# 1_3.net
KiCad netlist of a schematic drawn in Altium Designer
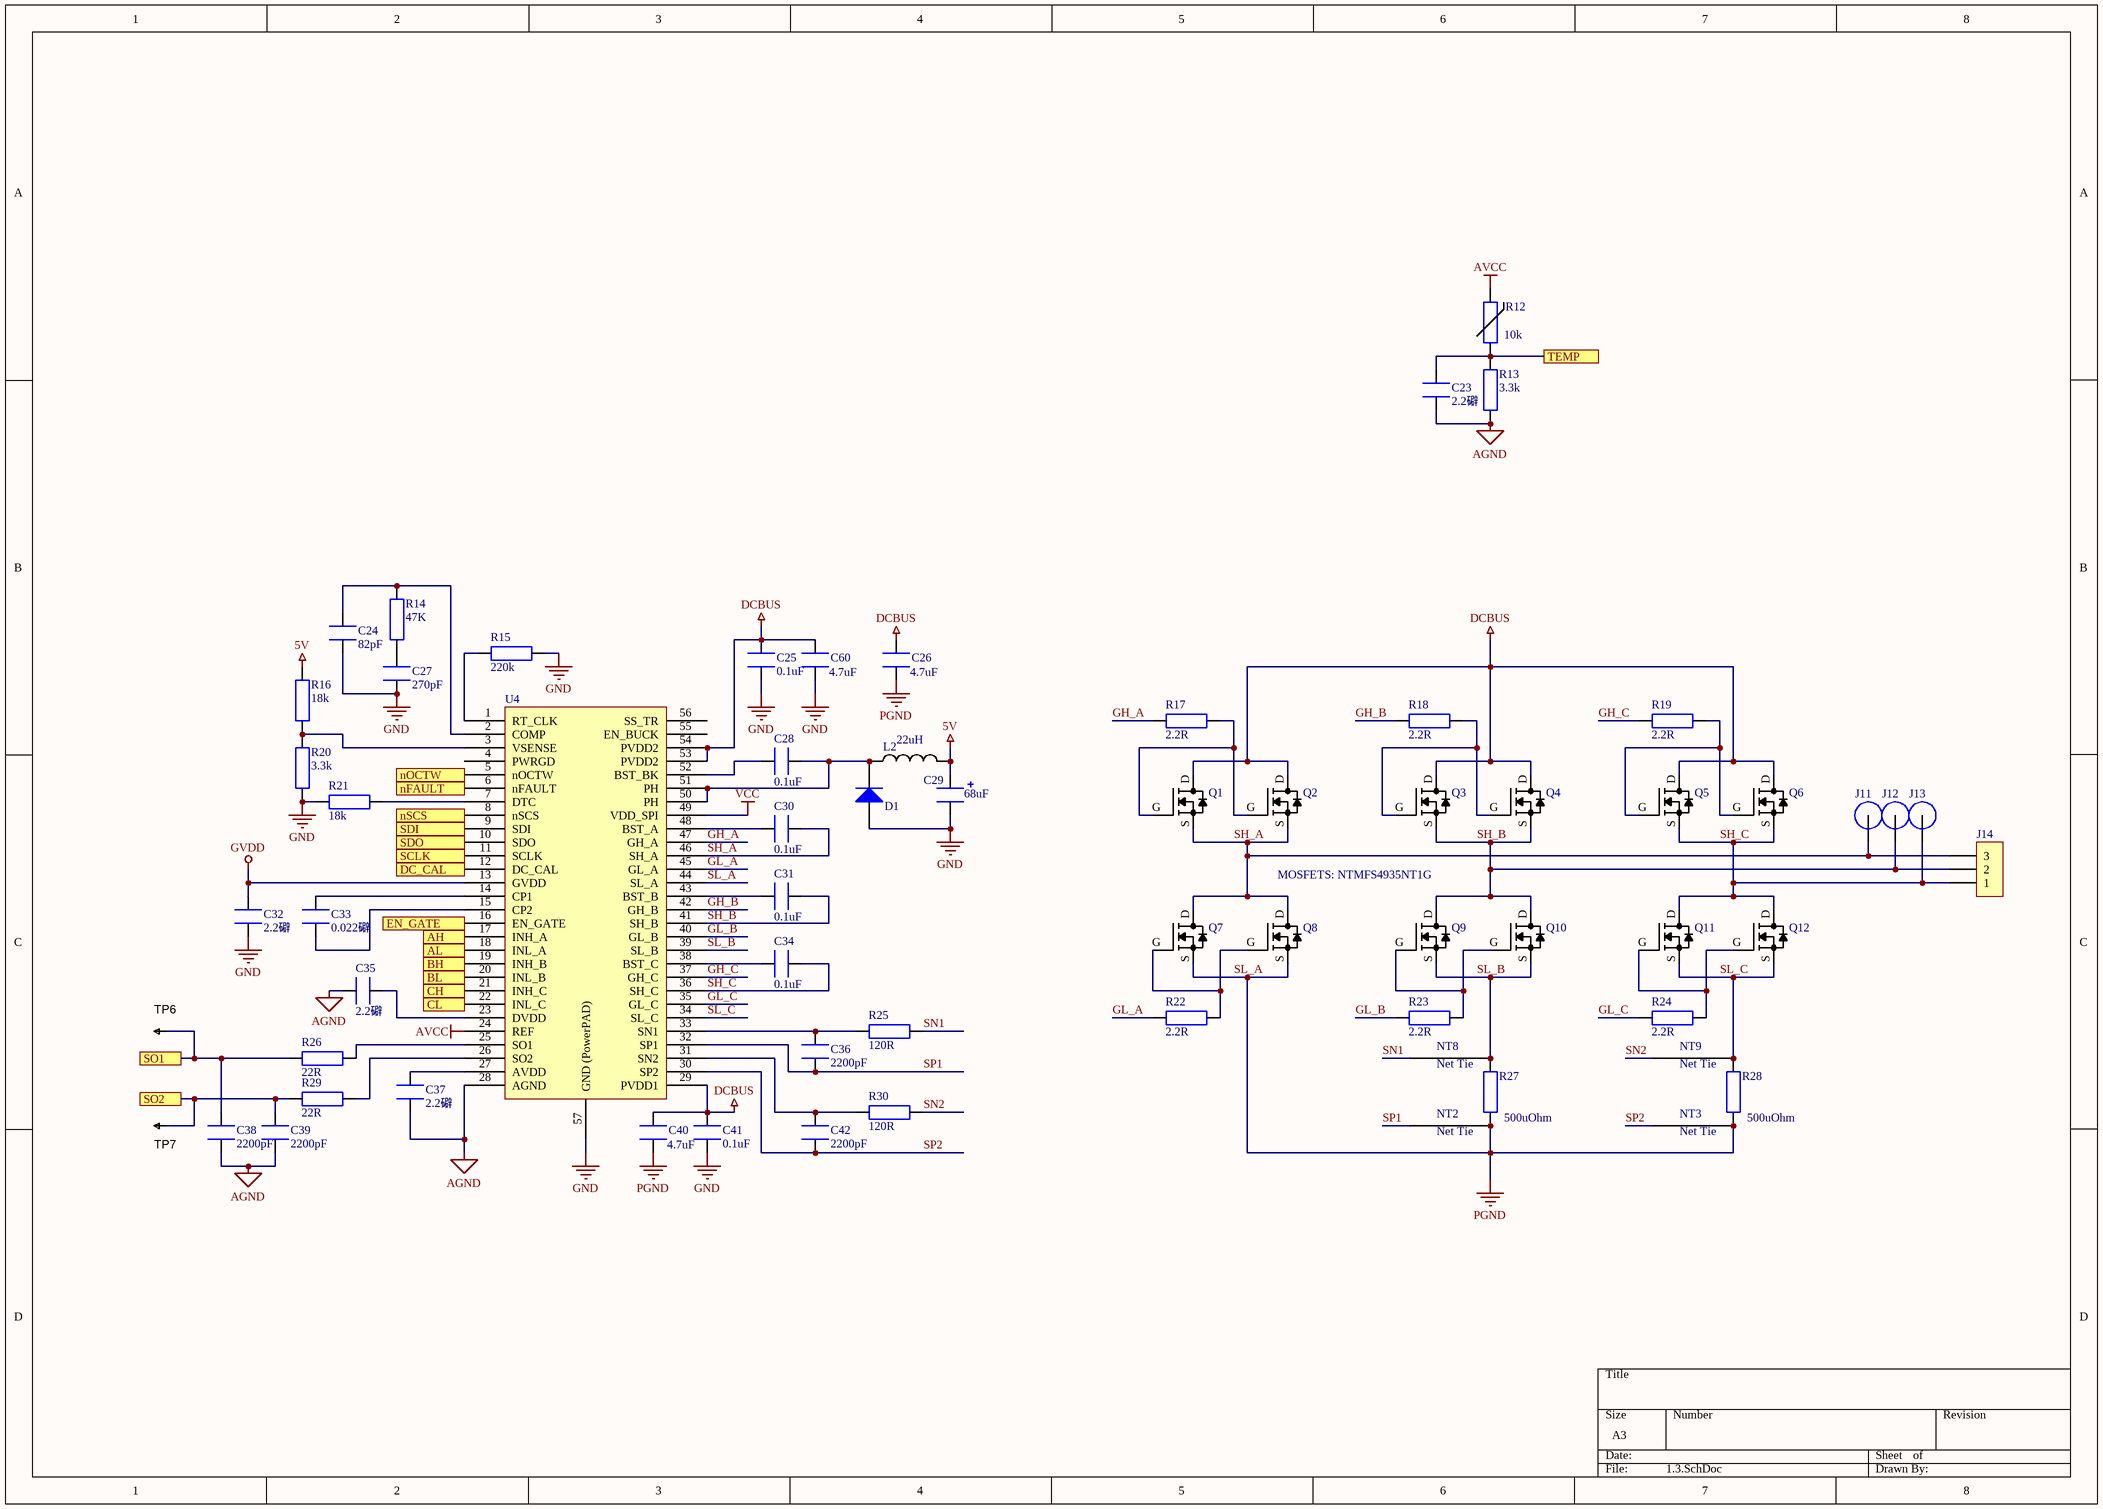
[diagram p0: 1.3.SchDoc]

(export (version "E")
  (design (tool "Eeschema 10.0.6"))
  (components
    (comp (ref "C23")
      (value "2.2礔")
      (footprint "CAPC1608X09L")
      (description "CAP CER 2.2UF 16V X5R 0603")
      (fields
        (field (name "MANUFACTURER") "Murata Electronics North America")
        (field (name "MANUFACTURER PART NUMBER") "GRM188R61C225KE15D")
      )
      (libsource (lib "CustomComponents") (part "GRM188R61C225KE15D"))
    )
    (comp (ref "C24")
      (value "82pF")
      (footprint "CAPC1608X09L")
      (description "CAP CER 82PF 100V NP0 0603")
      (fields
        (field (name "MANUFACTURER") "Murata Electronics North America")
        (field (name "MANUFACTURER PART NUMBER") "GRM1885C2A820JA01D")
      )
      (libsource (lib "CustomComponents") (part "GRM1885C2A820JA01D"))
    )
    (comp (ref "C25")
      (value "0.1uF")
      (footprint "CAPC1608X09L")
      (description "CAP CER 0.1UF 50V X7R 0603")
      (fields
        (field (name "MANUFACTURER") "Murata Electronics North America")
        (field (name "MANUFACTURER PART NUMBER") "GRM188R71H104KA93D")
      )
      (libsource (lib "CustomComponents") (part "GRM188R71H104KA93D"))
    )
    (comp (ref "C26")
      (value "4.7uF")
      (footprint "CAPC2012X09N")
      (description "CAP CER 4.7UF 35V X5R 0805")
      (fields
        (field (name "MANUFACTURER") "Murata Electronics North America")
        (field (name "TOLERANCE") "?0%")
      )
      (libsource (lib "CustomComponents") (part "GRM219R6YA475KA73D"))
    )
    (comp (ref "C27")
      (value "270pF")
      (footprint "CAPC1608X09L")
      (description "CAP CER 270PF 50V NP0 0603")
      (fields
        (field (name "MANUFACTURER") "Murata Electronics North America")
        (field (name "MANUFACTURER PART NUMBER") "GRM1885C1H271JA01D")
      )
      (libsource (lib "CustomComponents") (part "GRM1885C1H271JA01D"))
    )
    (comp (ref "C28")
      (value "0.1uF")
      (footprint "CAPC1608X09L")
      (description "CAP CER 0.1UF 50V X7R 0603")
      (fields
        (field (name "MANUFACTURER") "Murata Electronics North America")
        (field (name "MANUFACTURER PART NUMBER") "GRM188R71H104KA93D")
      )
      (libsource (lib "CustomComponents") (part "GRM188R71H104KA93D"))
    )
    (comp (ref "C29")
      (value "68uF")
      (footprint "CAPCP6032X28N")
      (description "CAP TANT 68UF 16V 20% 2312 250mOhm")
      (fields (field (name "MANUFACTURER") "KEMET") (field (name "TOLERANCE") "?0%"))
      (libsource (lib "CustomComponents") (part "T495C686M016ATE250"))
    )
    (comp (ref "C30")
      (value "0.1uF")
      (footprint "CAPC1608X09L")
      (description "CAP CER 0.1UF 50V X7R 0603")
      (fields
        (field (name "MANUFACTURER") "Murata Electronics North America")
        (field (name "MANUFACTURER PART NUMBER") "GRM188R71H104KA93D")
      )
      (libsource (lib "CustomComponents") (part "GRM188R71H104KA93D"))
    )
    (comp (ref "C31")
      (value "0.1uF")
      (footprint "CAPC1608X09L")
      (description "CAP CER 0.1UF 50V X7R 0603")
      (fields
        (field (name "MANUFACTURER") "Murata Electronics North America")
        (field (name "MANUFACTURER PART NUMBER") "GRM188R71H104KA93D")
      )
      (libsource (lib "CustomComponents") (part "GRM188R71H104KA93D"))
    )
    (comp (ref "C32")
      (value "2.2礔")
      (footprint "CAPC1608X09L")
      (description "CAP CER 2.2UF 16V X5R 0603")
      (fields
        (field (name "MANUFACTURER") "Murata Electronics North America")
        (field (name "MANUFACTURER PART NUMBER") "GRM188R61C225KE15D")
      )
      (libsource (lib "CustomComponents") (part "GRM188R61C225KE15D"))
    )
    (comp (ref "C33")
      (value "0.022礔")
      (footprint "CAPC1608X09L")
      (description "CAP CER 0.022UF 50V X7R 0603")
      (fields
        (field (name "MANUFACTURER") "Murata Electronics North America")
        (field (name "MANUFACTURER PART NUMBER") "GRM188R71H223KA01D")
      )
      (libsource (lib "CustomComponents") (part "GRM188R71H223KA01D"))
    )
    (comp (ref "C34")
      (value "0.1uF")
      (footprint "CAPC1608X09L")
      (description "CAP CER 0.1UF 50V X7R 0603")
      (fields
        (field (name "MANUFACTURER") "Murata Electronics North America")
        (field (name "MANUFACTURER PART NUMBER") "GRM188R71H104KA93D")
      )
      (libsource (lib "CustomComponents") (part "GRM188R71H104KA93D"))
    )
    (comp (ref "C35")
      (value "2.2礔")
      (footprint "CAPC1608X09L")
      (description "CAP CER 2.2UF 16V X5R 0603")
      (fields
        (field (name "MANUFACTURER") "Murata Electronics North America")
        (field (name "MANUFACTURER PART NUMBER") "GRM188R61C225KE15D")
      )
      (libsource (lib "CustomComponents") (part "GRM188R61C225KE15D"))
    )
    (comp (ref "C36")
      (value "2200pF")
      (footprint "CAPC1608X09L")
      (description "CAP CER 2200PF 50V NP0 0603")
      (fields
        (field (name "MANUFACTURER") "Murata Electronics North America")
        (field (name "TOLERANCE") "?%")
      )
      (libsource (lib "CustomComponents") (part "GRM1885C1H222JA01D"))
    )
    (comp (ref "C37")
      (value "2.2礔")
      (footprint "CAPC1608X09L")
      (description "CAP CER 2.2UF 16V X5R 0603")
      (fields
        (field (name "MANUFACTURER") "Murata Electronics North America")
        (field (name "MANUFACTURER PART NUMBER") "GRM188R61C225KE15D")
      )
      (libsource (lib "CustomComponents") (part "GRM188R61C225KE15D"))
    )
    (comp (ref "C38")
      (value "2200pF")
      (footprint "CAPC1608X09L")
      (description "CAP CER 2200PF 50V NP0 0603")
      (fields
        (field (name "MANUFACTURER") "Murata Electronics North America")
        (field (name "TOLERANCE") "?%")
      )
      (libsource (lib "CustomComponents") (part "GRM1885C1H222JA01D"))
    )
    (comp (ref "C39")
      (value "2200pF")
      (footprint "CAPC1608X09L")
      (description "CAP CER 2200PF 50V NP0 0603")
      (fields
        (field (name "MANUFACTURER") "Murata Electronics North America")
        (field (name "TOLERANCE") "?%")
      )
      (libsource (lib "CustomComponents") (part "GRM1885C1H222JA01D"))
    )
    (comp (ref "C40")
      (value "4.7uF")
      (footprint "CAPC2012X09N")
      (description "CAP CER 4.7UF 35V X5R 0805")
      (fields
        (field (name "MANUFACTURER") "Murata Electronics North America")
        (field (name "TOLERANCE") "?0%")
      )
      (libsource (lib "CustomComponents") (part "GRM219R6YA475KA73D"))
    )
    (comp (ref "C41")
      (value "0.1uF")
      (footprint "CAPC1608X09L")
      (description "CAP CER 0.1UF 50V X7R 0603")
      (fields
        (field (name "MANUFACTURER") "Murata Electronics North America")
        (field (name "MANUFACTURER PART NUMBER") "GRM188R71H104KA93D")
      )
      (libsource (lib "CustomComponents") (part "GRM188R71H104KA93D"))
    )
    (comp (ref "C42")
      (value "2200pF")
      (footprint "CAPC1608X09L")
      (description "CAP CER 2200PF 50V NP0 0603")
      (fields
        (field (name "MANUFACTURER") "Murata Electronics North America")
        (field (name "TOLERANCE") "?%")
      )
      (libsource (lib "CustomComponents") (part "GRM1885C1H222JA01D"))
    )
    (comp (ref "C60")
      (value "4.7uF")
      (footprint "CAPC2012X09N")
      (description "CAP CER 4.7UF 35V X5R 0805")
      (fields
        (field (name "MANUFACTURER") "Murata Electronics North America")
        (field (name "TOLERANCE") "?0%")
      )
      (libsource (lib "CustomComponents") (part "GRM219R6YA475KA73D"))
    )
    (comp (ref "D1")
      (value "~")
      (footprint "DIOM2717X10N")
      (description "Rectifier Diode, Single, 40 V, 1 A, SOD-123FL, 2, 550 mV")
      (libsource (lib "CustomComponents") (part "MBR140SFT1G"))
    )
    (comp (ref "J11")
      (value "~")
      (footprint "M3 Spade Hole")
      (description "M3 Spade Terminal")
      (libsource (lib "CustomComponents") (part "M3 Spade Terminal"))
    )
    (comp (ref "J12")
      (value "~")
      (footprint "M3 Spade Hole")
      (description "M3 Spade Terminal")
      (libsource (lib "CustomComponents") (part "M3 Spade Terminal"))
    )
    (comp (ref "J13")
      (value "~")
      (footprint "M3 Spade Hole")
      (description "M3 Spade Terminal")
      (libsource (lib "CustomComponents") (part "M3 Spade Terminal"))
    )
    (comp (ref "J14")
      (value "1704936")
      (footprint "1704936")
      (description "CONN TERM BLOCK 3POS 7.62MM")
      (fields (field (name "MANUFACTURER") "Phoenix Contact") (field (name "VOLTAGE") "300V"))
      (libsource (lib "CustomComponents") (part "1704936"))
    )
    (comp (ref "L2")
      (value "22uH")
      (footprint "INDC6060X28N")
      (description "INDUCTOR 22UH 1.4A 175.5 MOHM")
      (libsource (lib "CustomComponents") (part "NR6028T220M"))
    )
    (comp (ref "NT2")
      (value "0.25mm")
      (footprint "NetTie_0.25mm")
      (libsource (lib "CustomComponents") (part "NetTie_0.25mm"))
    )
    (comp (ref "NT3")
      (value "0.25mm")
      (footprint "NetTie_0.25mm")
      (libsource (lib "CustomComponents") (part "NetTie_0.25mm"))
    )
    (comp (ref "NT8")
      (value "0.25mm")
      (footprint "NetTie_0.25mm")
      (libsource (lib "CustomComponents") (part "NetTie_0.25mm"))
    )
    (comp (ref "NT9")
      (value "0.25mm")
      (footprint "NetTie_0.25mm")
      (libsource (lib "CustomComponents") (part "NetTie_0.25mm"))
    )
    (comp (ref "Q1")
      (value "~")
      (footprint "SO8FL")
      (description "MOSFET N-CH 30V 13A SO8FL")
      (fields
        (field (name "MANUFACTURER") "ON Semiconductor")
        (field (name "MANUFACTURER PART NUMBER") "NTMFS4935NT1G")
      )
      (libsource (lib "CustomComponents") (part "NTMFS4935NT1G"))
    )
    (comp (ref "Q2")
      (value "FILL_FOOTPRINT")
      (footprint "SO8FL_FILL")
      (description "MOSFET N-CH 30V 13A SO8FL")
      (fields
        (field (name "MANUFACTURER") "ON Semiconductor")
        (field (name "MANUFACTURER PART NUMBER") "NTMFS4935NT1G")
      )
      (libsource (lib "CustomComponents") (part "NTMFS4935NT1G"))
    )
    (comp (ref "Q3")
      (value "~")
      (footprint "SO8FL")
      (description "MOSFET N-CH 30V 13A SO8FL")
      (fields
        (field (name "MANUFACTURER") "ON Semiconductor")
        (field (name "MANUFACTURER PART NUMBER") "NTMFS4935NT1G")
      )
      (libsource (lib "CustomComponents") (part "NTMFS4935NT1G"))
    )
    (comp (ref "Q4")
      (value "FILL_FOOTPRINT")
      (footprint "SO8FL_FILL")
      (description "MOSFET N-CH 30V 13A SO8FL")
      (fields
        (field (name "MANUFACTURER") "ON Semiconductor")
        (field (name "MANUFACTURER PART NUMBER") "NTMFS4935NT1G")
      )
      (libsource (lib "CustomComponents") (part "NTMFS4935NT1G"))
    )
    (comp (ref "Q5")
      (value "~")
      (footprint "SO8FL")
      (description "MOSFET N-CH 30V 13A SO8FL")
      (fields
        (field (name "MANUFACTURER") "ON Semiconductor")
        (field (name "MANUFACTURER PART NUMBER") "NTMFS4935NT1G")
      )
      (libsource (lib "CustomComponents") (part "NTMFS4935NT1G"))
    )
    (comp (ref "Q6")
      (value "FILL_FOOTPRINT")
      (footprint "SO8FL_FILL")
      (description "MOSFET N-CH 30V 13A SO8FL")
      (fields
        (field (name "MANUFACTURER") "ON Semiconductor")
        (field (name "MANUFACTURER PART NUMBER") "NTMFS4935NT1G")
      )
      (libsource (lib "CustomComponents") (part "NTMFS4935NT1G"))
    )
    (comp (ref "Q7")
      (value "~")
      (footprint "SO8FL")
      (description "MOSFET N-CH 30V 13A SO8FL")
      (fields
        (field (name "MANUFACTURER") "ON Semiconductor")
        (field (name "MANUFACTURER PART NUMBER") "NTMFS4935NT1G")
      )
      (libsource (lib "CustomComponents") (part "NTMFS4935NT1G"))
    )
    (comp (ref "Q8")
      (value "~")
      (footprint "SO8FL")
      (description "MOSFET N-CH 30V 13A SO8FL")
      (fields
        (field (name "MANUFACTURER") "ON Semiconductor")
        (field (name "MANUFACTURER PART NUMBER") "NTMFS4935NT1G")
      )
      (libsource (lib "CustomComponents") (part "NTMFS4935NT1G"))
    )
    (comp (ref "Q9")
      (value "~")
      (footprint "SO8FL")
      (description "MOSFET N-CH 30V 13A SO8FL")
      (fields
        (field (name "MANUFACTURER") "ON Semiconductor")
        (field (name "MANUFACTURER PART NUMBER") "NTMFS4935NT1G")
      )
      (libsource (lib "CustomComponents") (part "NTMFS4935NT1G"))
    )
    (comp (ref "Q10")
      (value "~")
      (footprint "SO8FL")
      (description "MOSFET N-CH 30V 13A SO8FL")
      (fields
        (field (name "MANUFACTURER") "ON Semiconductor")
        (field (name "MANUFACTURER PART NUMBER") "NTMFS4935NT1G")
      )
      (libsource (lib "CustomComponents") (part "NTMFS4935NT1G"))
    )
    (comp (ref "Q11")
      (value "~")
      (footprint "SO8FL")
      (description "MOSFET N-CH 30V 13A SO8FL")
      (fields
        (field (name "MANUFACTURER") "ON Semiconductor")
        (field (name "MANUFACTURER PART NUMBER") "NTMFS4935NT1G")
      )
      (libsource (lib "CustomComponents") (part "NTMFS4935NT1G"))
    )
    (comp (ref "Q12")
      (value "~")
      (footprint "SO8FL")
      (description "MOSFET N-CH 30V 13A SO8FL")
      (fields
        (field (name "MANUFACTURER") "ON Semiconductor")
        (field (name "MANUFACTURER PART NUMBER") "NTMFS4935NT1G")
      )
      (libsource (lib "CustomComponents") (part "NTMFS4935NT1G"))
    )
    (comp (ref "R12")
      (value "10k")
      (footprint "RESC1005X40N")
      (description "THERMISTOR 10K OHM NTC 0402 SMD")
      (libsource (lib "CustomComponents") (part "NCP15XH103F03RC"))
    )
    (comp (ref "R13")
      (value "3.3k")
      (footprint "RESC1608X55N")
      (description "RES SMD 3.3K OHM 1% 1/10W 0603")
      (fields
        (field (name "MANUFACTURER") "Yageo")
        (field (name "MANUFACTURER PART NUMBER") "RC0603FR-073K3L")
      )
      (libsource (lib "CustomComponents") (part "RC0603FR-073K3L"))
    )
    (comp (ref "R14")
      (value "47K")
      (footprint "RESC1608X55N")
      (description "RES SMD 47K OHM 1% 1/10W 0603")
      (fields
        (field (name "MANUFACTURER") "Yageo")
        (field (name "MANUFACTURER PART NUMBER") "RC0603FR-0747KL")
      )
      (libsource (lib "CustomComponents") (part "RC0603FR-0747KL"))
    )
    (comp (ref "R15")
      (value "220k")
      (footprint "RESC1608X55N")
      (description "RES SMD 220K OHM 1% 1/10W 0603")
      (fields
        (field (name "MANUFACTURER") "Yageo")
        (field (name "MANUFACTURER PART NUMBER") "RC0603FR-07220KL")
      )
      (libsource (lib "CustomComponents") (part "RC0603FR-07220KL"))
    )
    (comp (ref "R16")
      (value "18k")
      (footprint "RESC1608X55N")
      (description "RES SMD 18K OHM 1% 1/10W 0603")
      (fields
        (field (name "MANUFACTURER") "Yageo")
        (field (name "MANUFACTURER PART NUMBER") "RC0603FR-0718KL")
      )
      (libsource (lib "CustomComponents") (part "RC0603FR-0718KL"))
    )
    (comp (ref "R17")
      (value "2.2R")
      (footprint "RESC1608X55N")
      (description "RES SMD 2.2 OHM 1% 1/10W 0603")
      (fields
        (field (name "MANUFACTURER") "Yageo")
        (field (name "MANUFACTURER PART NUMBER") "RC0603FR-072R2L")
      )
      (libsource (lib "CustomComponents") (part "RC0603FR-072R2L"))
    )
    (comp (ref "R18")
      (value "2.2R")
      (footprint "RESC1608X55N")
      (description "RES SMD 2.2 OHM 1% 1/10W 0603")
      (fields
        (field (name "MANUFACTURER") "Yageo")
        (field (name "MANUFACTURER PART NUMBER") "RC0603FR-072R2L")
      )
      (libsource (lib "CustomComponents") (part "RC0603FR-072R2L"))
    )
    (comp (ref "R19")
      (value "2.2R")
      (footprint "RESC1608X55N")
      (description "RES SMD 2.2 OHM 1% 1/10W 0603")
      (fields
        (field (name "MANUFACTURER") "Yageo")
        (field (name "MANUFACTURER PART NUMBER") "RC0603FR-072R2L")
      )
      (libsource (lib "CustomComponents") (part "RC0603FR-072R2L"))
    )
    (comp (ref "R20")
      (value "3.3k")
      (footprint "RESC1608X55N")
      (description "RES SMD 3.3K OHM 1% 1/10W 0603")
      (fields
        (field (name "MANUFACTURER") "Yageo")
        (field (name "MANUFACTURER PART NUMBER") "RC0603FR-073K3L")
      )
      (libsource (lib "CustomComponents") (part "RC0603FR-073K3L"))
    )
    (comp (ref "R21")
      (value "18k")
      (footprint "RESC1608X55N")
      (description "RES SMD 18K OHM 1% 1/10W 0603")
      (fields
        (field (name "MANUFACTURER") "Yageo")
        (field (name "MANUFACTURER PART NUMBER") "RC0603FR-0718KL")
      )
      (libsource (lib "CustomComponents") (part "RC0603FR-0718KL"))
    )
    (comp (ref "R22")
      (value "2.2R")
      (footprint "RESC1608X55N")
      (description "RES SMD 2.2 OHM 1% 1/10W 0603")
      (fields
        (field (name "MANUFACTURER") "Yageo")
        (field (name "MANUFACTURER PART NUMBER") "RC0603FR-072R2L")
      )
      (libsource (lib "CustomComponents") (part "RC0603FR-072R2L"))
    )
    (comp (ref "R23")
      (value "2.2R")
      (footprint "RESC1608X55N")
      (description "RES SMD 2.2 OHM 1% 1/10W 0603")
      (fields
        (field (name "MANUFACTURER") "Yageo")
        (field (name "MANUFACTURER PART NUMBER") "RC0603FR-072R2L")
      )
      (libsource (lib "CustomComponents") (part "RC0603FR-072R2L"))
    )
    (comp (ref "R24")
      (value "2.2R")
      (footprint "RESC1608X55N")
      (description "RES SMD 2.2 OHM 1% 1/10W 0603")
      (fields
        (field (name "MANUFACTURER") "Yageo")
        (field (name "MANUFACTURER PART NUMBER") "RC0603FR-072R2L")
      )
      (libsource (lib "CustomComponents") (part "RC0603FR-072R2L"))
    )
    (comp (ref "R25")
      (value "120R")
      (footprint "RESC1608X55N")
      (description "RES SMD 120 OHM 1% 1/10W 0603")
      (fields
        (field (name "MANUFACTURER") "Yageo")
        (field (name "MANUFACTURER PART NUMBER") "RC0603FR-07120RL")
      )
      (libsource (lib "CustomComponents") (part "RC0603FR-07120RL"))
    )
    (comp (ref "R26")
      (value "22R")
      (footprint "RESC1608X55N")
      (description "RES SMD 22 OHM 1% 1/10W 0603")
      (fields
        (field (name "MANUFACTURER") "Yageo")
        (field (name "MANUFACTURER PART NUMBER") "RC0603FR-0722RL")
      )
      (libsource (lib "CustomComponents") (part "RC0603FR-0722RL"))
    )
    (comp (ref "R27")
      (value "500uOhm")
      (footprint "RESC6432X09N")
      (description "RES SMD 0.0005 OHM 1% 3W 2512")
      (fields (field (name "MANUFACTURER") "Riedon") (field (name "TOLERANCE") "?%"))
      (libsource (lib "CustomComponents") (part "CSR2512C0R0005F"))
    )
    (comp (ref "R28")
      (value "500uOhm")
      (footprint "RESC6432X09N")
      (description "RES SMD 0.0005 OHM 1% 3W 2512")
      (fields (field (name "MANUFACTURER") "Riedon") (field (name "TOLERANCE") "?%"))
      (libsource (lib "CustomComponents") (part "CSR2512C0R0005F"))
    )
    (comp (ref "R29")
      (value "22R")
      (footprint "RESC1608X55N")
      (description "RES SMD 22 OHM 1% 1/10W 0603")
      (fields
        (field (name "MANUFACTURER") "Yageo")
        (field (name "MANUFACTURER PART NUMBER") "RC0603FR-0722RL")
      )
      (libsource (lib "CustomComponents") (part "RC0603FR-0722RL"))
    )
    (comp (ref "R30")
      (value "120R")
      (footprint "RESC1608X55N")
      (description "RES SMD 120 OHM 1% 1/10W 0603")
      (fields
        (field (name "MANUFACTURER") "Yageo")
        (field (name "MANUFACTURER PART NUMBER") "RC0603FR-07120RL")
      )
      (libsource (lib "CustomComponents") (part "RC0603FR-07120RL"))
    )
    (comp (ref "TP6")
      (value "TESTPOINT")
      (footprint "TP-R30")
      (description "SMD test pin")
      (libsource (lib "PBL - Test Points") (part "TESTPOINT"))
    )
    (comp (ref "TP7")
      (value "TESTPOINT")
      (footprint "TP-R30")
      (description "SMD test pin")
      (libsource (lib "PBL - Test Points") (part "TESTPOINT"))
    )
    (comp (ref "U4")
      (value "~")
      (footprint "TSSOP50P810X120_HS-57N")
      (description "MOTOR DRIVER, 3PH, 56HTSSOP")
      (libsource (lib "CustomComponents") (part "DRV8301"))
    )
  )
  (nets
    (net (code "1") (name "/AH") (class "Default")
      (node (ref "U4") (pin "17") (pinfunction "INH_A_17") (pintype "passive"))
    )
    (net (code "2") (name "/AL") (class "Default")
      (node (ref "U4") (pin "18") (pinfunction "INL_A_18") (pintype "passive"))
    )
    (net (code "3") (name "/BH") (class "Default")
      (node (ref "U4") (pin "19") (pinfunction "INH_B_19") (pintype "passive"))
    )
    (net (code "4") (name "/BL") (class "Default")
      (node (ref "U4") (pin "20") (pinfunction "INL_B_20") (pintype "passive"))
    )
    (net (code "5") (name "/CH") (class "Default")
      (node (ref "U4") (pin "21") (pinfunction "INH_C_21") (pintype "passive"))
    )
    (net (code "6") (name "/CL") (class "Default")
      (node (ref "U4") (pin "22") (pinfunction "INL_C_22") (pintype "passive"))
    )
    (net (code "7") (name "/DC_CAL") (class "Default")
      (node (ref "U4") (pin "12") (pinfunction "DC_CAL_12") (pintype "passive"))
    )
    (net (code "8") (name "/EN_GATE") (class "Default")
      (node (ref "U4") (pin "16") (pinfunction "EN_GATE_16") (pintype "passive"))
    )
    (net (code "9") (name "/GH_A") (class "Default")
      (node (ref "R17") (pin "2") (pinfunction "0_2") (pintype "passive"))
      (node (ref "U4") (pin "47") (pinfunction "GH_A_47") (pintype "passive"))
    )
    (net (code "10") (name "/GH_B") (class "Default")
      (node (ref "R18") (pin "2") (pinfunction "0_2") (pintype "passive"))
      (node (ref "U4") (pin "42") (pinfunction "GH_B_42") (pintype "passive"))
    )
    (net (code "11") (name "/GH_C") (class "Default")
      (node (ref "R19") (pin "2") (pinfunction "0_2") (pintype "passive"))
      (node (ref "U4") (pin "37") (pinfunction "GH_C_37") (pintype "passive"))
    )
    (net (code "12") (name "/GL_A") (class "Default")
      (node (ref "R22") (pin "2") (pinfunction "0_2") (pintype "passive"))
      (node (ref "U4") (pin "45") (pinfunction "GL_A_45") (pintype "passive"))
    )
    (net (code "13") (name "/GL_B") (class "Default")
      (node (ref "R23") (pin "2") (pinfunction "0_2") (pintype "passive"))
      (node (ref "U4") (pin "40") (pinfunction "GL_B_40") (pintype "passive"))
    )
    (net (code "14") (name "/GL_C") (class "Default")
      (node (ref "R24") (pin "2") (pinfunction "0_2") (pintype "passive"))
      (node (ref "U4") (pin "35") (pinfunction "GL_C_35") (pintype "passive"))
    )
    (net (code "15") (name "/SCLK") (class "Default")
      (node (ref "U4") (pin "11") (pinfunction "SCLK_11") (pintype "passive"))
    )
    (net (code "16") (name "/SDI") (class "Default")
      (node (ref "U4") (pin "9") (pinfunction "SDI_9") (pintype "passive"))
    )
    (net (code "17") (name "/SDO") (class "Default")
      (node (ref "U4") (pin "10") (pinfunction "SDO_10") (pintype "passive"))
    )
    (net (code "18") (name "/SH_A") (class "Default")
      (node (ref "C30") (pin "1") (pinfunction "1_1") (pintype "passive"))
      (node (ref "J11") (pin "1") (pinfunction "1_1") (pintype "passive"))
      (node (ref "J14") (pin "3") (pinfunction "3_3") (pintype "passive"))
      (node (ref "Q1") (pin "S") (pinfunction "S_S") (pintype "passive"))
      (node (ref "Q2") (pin "S") (pinfunction "S_S") (pintype "passive"))
      (node (ref "Q7") (pin "D") (pinfunction "D_D") (pintype "passive"))
      (node (ref "Q8") (pin "D") (pinfunction "D_D") (pintype "passive"))
      (node (ref "U4") (pin "46") (pinfunction "SH_A_46") (pintype "passive"))
    )
    (net (code "19") (name "/SH_B") (class "Default")
      (node (ref "C31") (pin "1") (pinfunction "1_1") (pintype "passive"))
      (node (ref "J12") (pin "1") (pinfunction "1_1") (pintype "passive"))
      (node (ref "J14") (pin "2") (pinfunction "2_2") (pintype "passive"))
      (node (ref "Q10") (pin "D") (pinfunction "D_D") (pintype "passive"))
      (node (ref "Q3") (pin "S") (pinfunction "S_S") (pintype "passive"))
      (node (ref "Q4") (pin "S") (pinfunction "S_S") (pintype "passive"))
      (node (ref "Q9") (pin "D") (pinfunction "D_D") (pintype "passive"))
      (node (ref "U4") (pin "41") (pinfunction "SH_B_41") (pintype "passive"))
    )
    (net (code "20") (name "/SH_C") (class "Default")
      (node (ref "C34") (pin "1") (pinfunction "1_1") (pintype "passive"))
      (node (ref "J13") (pin "1") (pinfunction "1_1") (pintype "passive"))
      (node (ref "J14") (pin "1") (pinfunction "1_1") (pintype "passive"))
      (node (ref "Q11") (pin "D") (pinfunction "D_D") (pintype "passive"))
      (node (ref "Q12") (pin "D") (pinfunction "D_D") (pintype "passive"))
      (node (ref "Q5") (pin "S") (pinfunction "S_S") (pintype "passive"))
      (node (ref "Q6") (pin "S") (pinfunction "S_S") (pintype "passive"))
      (node (ref "U4") (pin "36") (pinfunction "SH_C_36") (pintype "passive"))
    )
    (net (code "21") (name "/SL_B") (class "Default")
      (node (ref "NT8") (pin "2") (pintype "passive"))
      (node (ref "Q10") (pin "S") (pinfunction "S_S") (pintype "passive"))
      (node (ref "Q9") (pin "S") (pinfunction "S_S") (pintype "passive"))
      (node (ref "R27") (pin "2") (pinfunction "0_2") (pintype "passive"))
      (node (ref "U4") (pin "39") (pinfunction "SL_B_39") (pintype "passive"))
    )
    (net (code "22") (name "/SL_C") (class "Default")
      (node (ref "NT9") (pin "2") (pintype "passive"))
      (node (ref "Q11") (pin "S") (pinfunction "S_S") (pintype "passive"))
      (node (ref "Q12") (pin "S") (pinfunction "S_S") (pintype "passive"))
      (node (ref "R28") (pin "2") (pinfunction "0_2") (pintype "passive"))
      (node (ref "U4") (pin "34") (pinfunction "SL_C_34") (pintype "passive"))
    )
    (net (code "23") (name "/SN1") (class "Default")
      (node (ref "NT8") (pin "1") (pintype "passive"))
      (node (ref "R25") (pin "1") (pinfunction "0_1") (pintype "passive"))
    )
    (net (code "24") (name "/SN2") (class "Default")
      (node (ref "NT9") (pin "1") (pintype "passive"))
      (node (ref "R30") (pin "1") (pinfunction "0_1") (pintype "passive"))
    )
    (net (code "25") (name "/SO1") (class "Default")
      (node (ref "C38") (pin "1") (pinfunction "1_1") (pintype "passive"))
      (node (ref "R26") (pin "2") (pinfunction "0_2") (pintype "passive"))
      (node (ref "TP6") (pin "1") (pintype "passive"))
    )
    (net (code "26") (name "/SO2") (class "Default")
      (node (ref "C39") (pin "1") (pinfunction "1_1") (pintype "passive"))
      (node (ref "R29") (pin "2") (pinfunction "0_2") (pintype "passive"))
      (node (ref "TP7") (pin "1") (pintype "passive"))
    )
    (net (code "27") (name "/SP1") (class "Default")
      (node (ref "C36") (pin "2") (pinfunction "2_2") (pintype "passive"))
      (node (ref "NT2") (pin "1") (pintype "passive"))
      (node (ref "U4") (pin "32") (pinfunction "SP1_32") (pintype "passive"))
    )
    (net (code "28") (name "/SP2") (class "Default")
      (node (ref "C42") (pin "2") (pinfunction "2_2") (pintype "passive"))
      (node (ref "NT3") (pin "1") (pintype "passive"))
      (node (ref "U4") (pin "30") (pinfunction "SP2_30") (pintype "passive"))
    )
    (net (code "29") (name "/TEMP") (class "Default")
      (node (ref "C23") (pin "2") (pinfunction "2_2") (pintype "passive"))
      (node (ref "R12") (pin "1") (pinfunction "0_1") (pintype "passive"))
      (node (ref "R13") (pin "1") (pinfunction "0_1") (pintype "passive"))
    )
    (net (code "30") (name "/nFAULT") (class "Default")
      (node (ref "U4") (pin "6") (pinfunction "nFAULT_6") (pintype "passive"))
    )
    (net (code "31") (name "/nOCTW") (class "Default")
      (node (ref "U4") (pin "5") (pinfunction "nOCTW_5") (pintype "passive"))
    )
    (net (code "32") (name "/nSCS") (class "Default")
      (node (ref "U4") (pin "8") (pinfunction "nSCS_8") (pintype "passive"))
    )
    (net (code "33") (name "5V") (class "Default")
      (node (ref "C29") (pin "1") (pinfunction "1_1") (pintype "passive"))
      (node (ref "L2") (pin "2") (pinfunction "2_2") (pintype "passive"))
      (node (ref "R16") (pin "1") (pinfunction "0_1") (pintype "passive"))
    )
    (net (code "34") (name "AGND") (class "Default")
      (node (ref "C23") (pin "1") (pinfunction "1_1") (pintype "passive"))
      (node (ref "C35") (pin "1") (pinfunction "1_1") (pintype "passive"))
      (node (ref "C37") (pin "1") (pinfunction "1_1") (pintype "passive"))
      (node (ref "C38") (pin "2") (pinfunction "2_2") (pintype "passive"))
      (node (ref "C39") (pin "2") (pinfunction "2_2") (pintype "passive"))
      (node (ref "R13") (pin "2") (pinfunction "0_2") (pintype "passive"))
      (node (ref "U4") (pin "28") (pinfunction "AGND_28") (pintype "passive"))
    )
    (net (code "35") (name "AVCC") (class "Default")
      (node (ref "R12") (pin "2") (pinfunction "0_2") (pintype "passive"))
      (node (ref "U4") (pin "24") (pinfunction "REF_24") (pintype "passive"))
    )
    (net (code "36") (name "DCBUS") (class "Default")
      (node (ref "C25") (pin "1") (pinfunction "1_1") (pintype "passive"))
      (node (ref "C26") (pin "2") (pinfunction "2_2") (pintype "passive"))
      (node (ref "C40") (pin "2") (pinfunction "2_2") (pintype "passive"))
      (node (ref "C41") (pin "1") (pinfunction "1_1") (pintype "passive"))
      (node (ref "C60") (pin "2") (pinfunction "2_2") (pintype "passive"))
      (node (ref "Q1") (pin "D") (pinfunction "D_D") (pintype "passive"))
      (node (ref "Q2") (pin "D") (pinfunction "D_D") (pintype "passive"))
      (node (ref "Q3") (pin "D") (pinfunction "D_D") (pintype "passive"))
      (node (ref "Q4") (pin "D") (pinfunction "D_D") (pintype "passive"))
      (node (ref "Q5") (pin "D") (pinfunction "D_D") (pintype "passive"))
      (node (ref "Q6") (pin "D") (pinfunction "D_D") (pintype "passive"))
      (node (ref "U4") (pin "29") (pinfunction "PVDD1_29") (pintype "passive"))
      (node (ref "U4") (pin "53") (pinfunction "PVDD2_53") (pintype "passive"))
      (node (ref "U4") (pin "54") (pinfunction "PVDD2_54") (pintype "passive"))
    )
    (net (code "37") (name "GND") (class "Default")
      (node (ref "C24") (pin "2") (pinfunction "2_2") (pintype "passive"))
      (node (ref "C25") (pin "2") (pinfunction "2_2") (pintype "passive"))
      (node (ref "C27") (pin "2") (pinfunction "2_2") (pintype "passive"))
      (node (ref "C29") (pin "2") (pinfunction "2_2") (pintype "passive"))
      (node (ref "C32") (pin "1") (pinfunction "1_1") (pintype "passive"))
      (node (ref "C41") (pin "2") (pinfunction "2_2") (pintype "passive"))
      (node (ref "C60") (pin "1") (pinfunction "1_1") (pintype "passive"))
      (node (ref "D1") (pin "A") (pinfunction "A_A") (pintype "passive"))
      (node (ref "R15") (pin "2") (pinfunction "0_2") (pintype "passive"))
      (node (ref "R20") (pin "2") (pinfunction "0_2") (pintype "passive"))
      (node (ref "R21") (pin "2") (pinfunction "0_2") (pintype "passive"))
      (node (ref "U4") (pin "57") (pinfunction "GND_(PowerPAD)_57") (pintype "passive"))
    )
    (net (code "38") (name "GVDD") (class "Default")
      (node (ref "C32") (pin "2") (pinfunction "2_2") (pintype "passive"))
      (node (ref "U4") (pin "13") (pinfunction "GVDD_13") (pintype "passive"))
    )
    (net (code "39") (name "Net-(C27-Pad1)") (class "Default")
      (node (ref "C27") (pin "1") (pinfunction "1_1") (pintype "passive"))
      (node (ref "R14") (pin "2") (pinfunction "0_2") (pintype "passive"))
    )
    (net (code "40") (name "Net-(C28-Pad1)") (class "Default")
      (node (ref "C28") (pin "1") (pinfunction "1_1") (pintype "passive"))
      (node (ref "D1") (pin "K") (pinfunction "K_K") (pintype "passive"))
      (node (ref "L2") (pin "1") (pinfunction "1_1") (pintype "passive"))
      (node (ref "U4") (pin "50") (pinfunction "PH_50") (pintype "passive"))
      (node (ref "U4") (pin "51") (pinfunction "PH_51") (pintype "passive"))
    )
    (net (code "41") (name "Net-(Q1-PadG)") (class "Default")
      (node (ref "Q1") (pin "G") (pinfunction "G_G") (pintype "passive"))
      (node (ref "Q2") (pin "G") (pinfunction "G_G") (pintype "passive"))
      (node (ref "R17") (pin "1") (pinfunction "0_1") (pintype "passive"))
    )
    (net (code "42") (name "Net-(Q3-PadG)") (class "Default")
      (node (ref "Q3") (pin "G") (pinfunction "G_G") (pintype "passive"))
      (node (ref "Q4") (pin "G") (pinfunction "G_G") (pintype "passive"))
      (node (ref "R18") (pin "1") (pinfunction "0_1") (pintype "passive"))
    )
    (net (code "43") (name "Net-(Q5-PadG)") (class "Default")
      (node (ref "Q5") (pin "G") (pinfunction "G_G") (pintype "passive"))
      (node (ref "Q6") (pin "G") (pinfunction "G_G") (pintype "passive"))
      (node (ref "R19") (pin "1") (pinfunction "0_1") (pintype "passive"))
    )
    (net (code "44") (name "Net-(Q7-PadG)") (class "Default")
      (node (ref "Q7") (pin "G") (pinfunction "G_G") (pintype "passive"))
      (node (ref "Q8") (pin "G") (pinfunction "G_G") (pintype "passive"))
      (node (ref "R22") (pin "1") (pinfunction "0_1") (pintype "passive"))
    )
    (net (code "45") (name "Net-(Q10-PadG)") (class "Default")
      (node (ref "Q10") (pin "G") (pinfunction "G_G") (pintype "passive"))
      (node (ref "Q9") (pin "G") (pinfunction "G_G") (pintype "passive"))
      (node (ref "R23") (pin "1") (pinfunction "0_1") (pintype "passive"))
    )
    (net (code "46") (name "Net-(Q11-PadG)") (class "Default")
      (node (ref "Q11") (pin "G") (pinfunction "G_G") (pintype "passive"))
      (node (ref "Q12") (pin "G") (pinfunction "G_G") (pintype "passive"))
      (node (ref "R24") (pin "1") (pinfunction "0_1") (pintype "passive"))
    )
    (net (code "47") (name "Net-(U4-AVDD)") (class "Default")
      (node (ref "C37") (pin "2") (pinfunction "2_2") (pintype "passive"))
      (node (ref "U4") (pin "27") (pinfunction "AVDD_27") (pintype "passive"))
    )
    (net (code "48") (name "Net-(U4-BST_A)") (class "Default")
      (node (ref "C30") (pin "2") (pinfunction "2_2") (pintype "passive"))
      (node (ref "U4") (pin "48") (pinfunction "BST_A_48") (pintype "passive"))
    )
    (net (code "49") (name "Net-(U4-BST_B)") (class "Default")
      (node (ref "C31") (pin "2") (pinfunction "2_2") (pintype "passive"))
      (node (ref "U4") (pin "43") (pinfunction "BST_B_43") (pintype "passive"))
    )
    (net (code "50") (name "Net-(U4-BST_BK)") (class "Default")
      (node (ref "C28") (pin "2") (pinfunction "2_2") (pintype "passive"))
      (node (ref "U4") (pin "52") (pinfunction "BST_BK_52") (pintype "passive"))
    )
    (net (code "51") (name "Net-(U4-BST_C)") (class "Default")
      (node (ref "C34") (pin "2") (pinfunction "2_2") (pintype "passive"))
      (node (ref "U4") (pin "38") (pinfunction "BST_C_38") (pintype "passive"))
    )
    (net (code "52") (name "Net-(U4-COMP)") (class "Default")
      (node (ref "C24") (pin "1") (pinfunction "1_1") (pintype "passive"))
      (node (ref "R14") (pin "1") (pinfunction "0_1") (pintype "passive"))
      (node (ref "U4") (pin "2") (pinfunction "COMP_2") (pintype "passive"))
    )
    (net (code "53") (name "Net-(U4-CP1)") (class "Default")
      (node (ref "C33") (pin "1") (pinfunction "1_1") (pintype "passive"))
      (node (ref "U4") (pin "14") (pinfunction "CP1_14") (pintype "passive"))
    )
    (net (code "54") (name "Net-(U4-CP2)") (class "Default")
      (node (ref "C33") (pin "2") (pinfunction "2_2") (pintype "passive"))
      (node (ref "U4") (pin "15") (pinfunction "CP2_15") (pintype "passive"))
    )
    (net (code "55") (name "Net-(U4-DTC)") (class "Default")
      (node (ref "R21") (pin "1") (pinfunction "0_1") (pintype "passive"))
      (node (ref "U4") (pin "7") (pinfunction "DTC_7") (pintype "passive"))
    )
    (net (code "56") (name "Net-(U4-DVDD)") (class "Default")
      (node (ref "C35") (pin "2") (pinfunction "2_2") (pintype "passive"))
      (node (ref "U4") (pin "23") (pinfunction "DVDD_23") (pintype "passive"))
    )
    (net (code "57") (name "Net-(U4-RT_CLK)") (class "Default")
      (node (ref "R15") (pin "1") (pinfunction "0_1") (pintype "passive"))
      (node (ref "U4") (pin "1") (pinfunction "RT_CLK_1") (pintype "passive"))
    )
    (net (code "58") (name "Net-(U4-SN1)") (class "Default")
      (node (ref "C36") (pin "1") (pinfunction "1_1") (pintype "passive"))
      (node (ref "R25") (pin "2") (pinfunction "0_2") (pintype "passive"))
      (node (ref "U4") (pin "33") (pinfunction "SN1_33") (pintype "passive"))
    )
    (net (code "59") (name "Net-(U4-SN2)") (class "Default")
      (node (ref "C42") (pin "1") (pinfunction "1_1") (pintype "passive"))
      (node (ref "R30") (pin "2") (pinfunction "0_2") (pintype "passive"))
      (node (ref "U4") (pin "31") (pinfunction "SN2_31") (pintype "passive"))
    )
    (net (code "60") (name "Net-(U4-SO1)") (class "Default")
      (node (ref "R26") (pin "1") (pinfunction "0_1") (pintype "passive"))
      (node (ref "U4") (pin "25") (pinfunction "SO1_25") (pintype "passive"))
    )
    (net (code "61") (name "Net-(U4-SO2)") (class "Default")
      (node (ref "R29") (pin "1") (pinfunction "0_1") (pintype "passive"))
      (node (ref "U4") (pin "26") (pinfunction "SO2_26") (pintype "passive"))
    )
    (net (code "62") (name "Net-(U4-VSENSE)") (class "Default")
      (node (ref "R16") (pin "2") (pinfunction "0_2") (pintype "passive"))
      (node (ref "R20") (pin "1") (pinfunction "0_1") (pintype "passive"))
      (node (ref "U4") (pin "3") (pinfunction "VSENSE_3") (pintype "passive"))
    )
    (net (code "63") (name "PGND") (class "Default")
      (node (ref "C26") (pin "1") (pinfunction "1_1") (pintype "passive"))
      (node (ref "C40") (pin "1") (pinfunction "1_1") (pintype "passive"))
      (node (ref "NT2") (pin "2") (pintype "passive"))
      (node (ref "NT3") (pin "2") (pintype "passive"))
      (node (ref "Q7") (pin "S") (pinfunction "S_S") (pintype "passive"))
      (node (ref "Q8") (pin "S") (pinfunction "S_S") (pintype "passive"))
      (node (ref "R27") (pin "1") (pinfunction "0_1") (pintype "passive"))
      (node (ref "R28") (pin "1") (pinfunction "0_1") (pintype "passive"))
      (node (ref "U4") (pin "44") (pinfunction "SL_A_44") (pintype "passive"))
    )
    (net (code "64") (name "VCC") (class "Default")
      (node (ref "U4") (pin "49") (pinfunction "VDD_SPI_49") (pintype "passive"))
    )
    (net (code "65") (name "unconnected-(U4-EN_BUCK-Pad55)") (class "Default")
      (node (ref "U4") (pin "55") (pinfunction "EN_BUCK_55") (pintype "passive"))
    )
    (net (code "66") (name "unconnected-(U4-PWRGD-Pad4)") (class "Default")
      (node (ref "U4") (pin "4") (pinfunction "PWRGD_4") (pintype "passive"))
    )
    (net (code "67") (name "unconnected-(U4-SS_TR-Pad56)") (class "Default")
      (node (ref "U4") (pin "56") (pinfunction "SS_TR_56") (pintype "passive"))
    )
  )
)
